# W705X.net
KiCad netlist of a schematic drawn in EAGLE
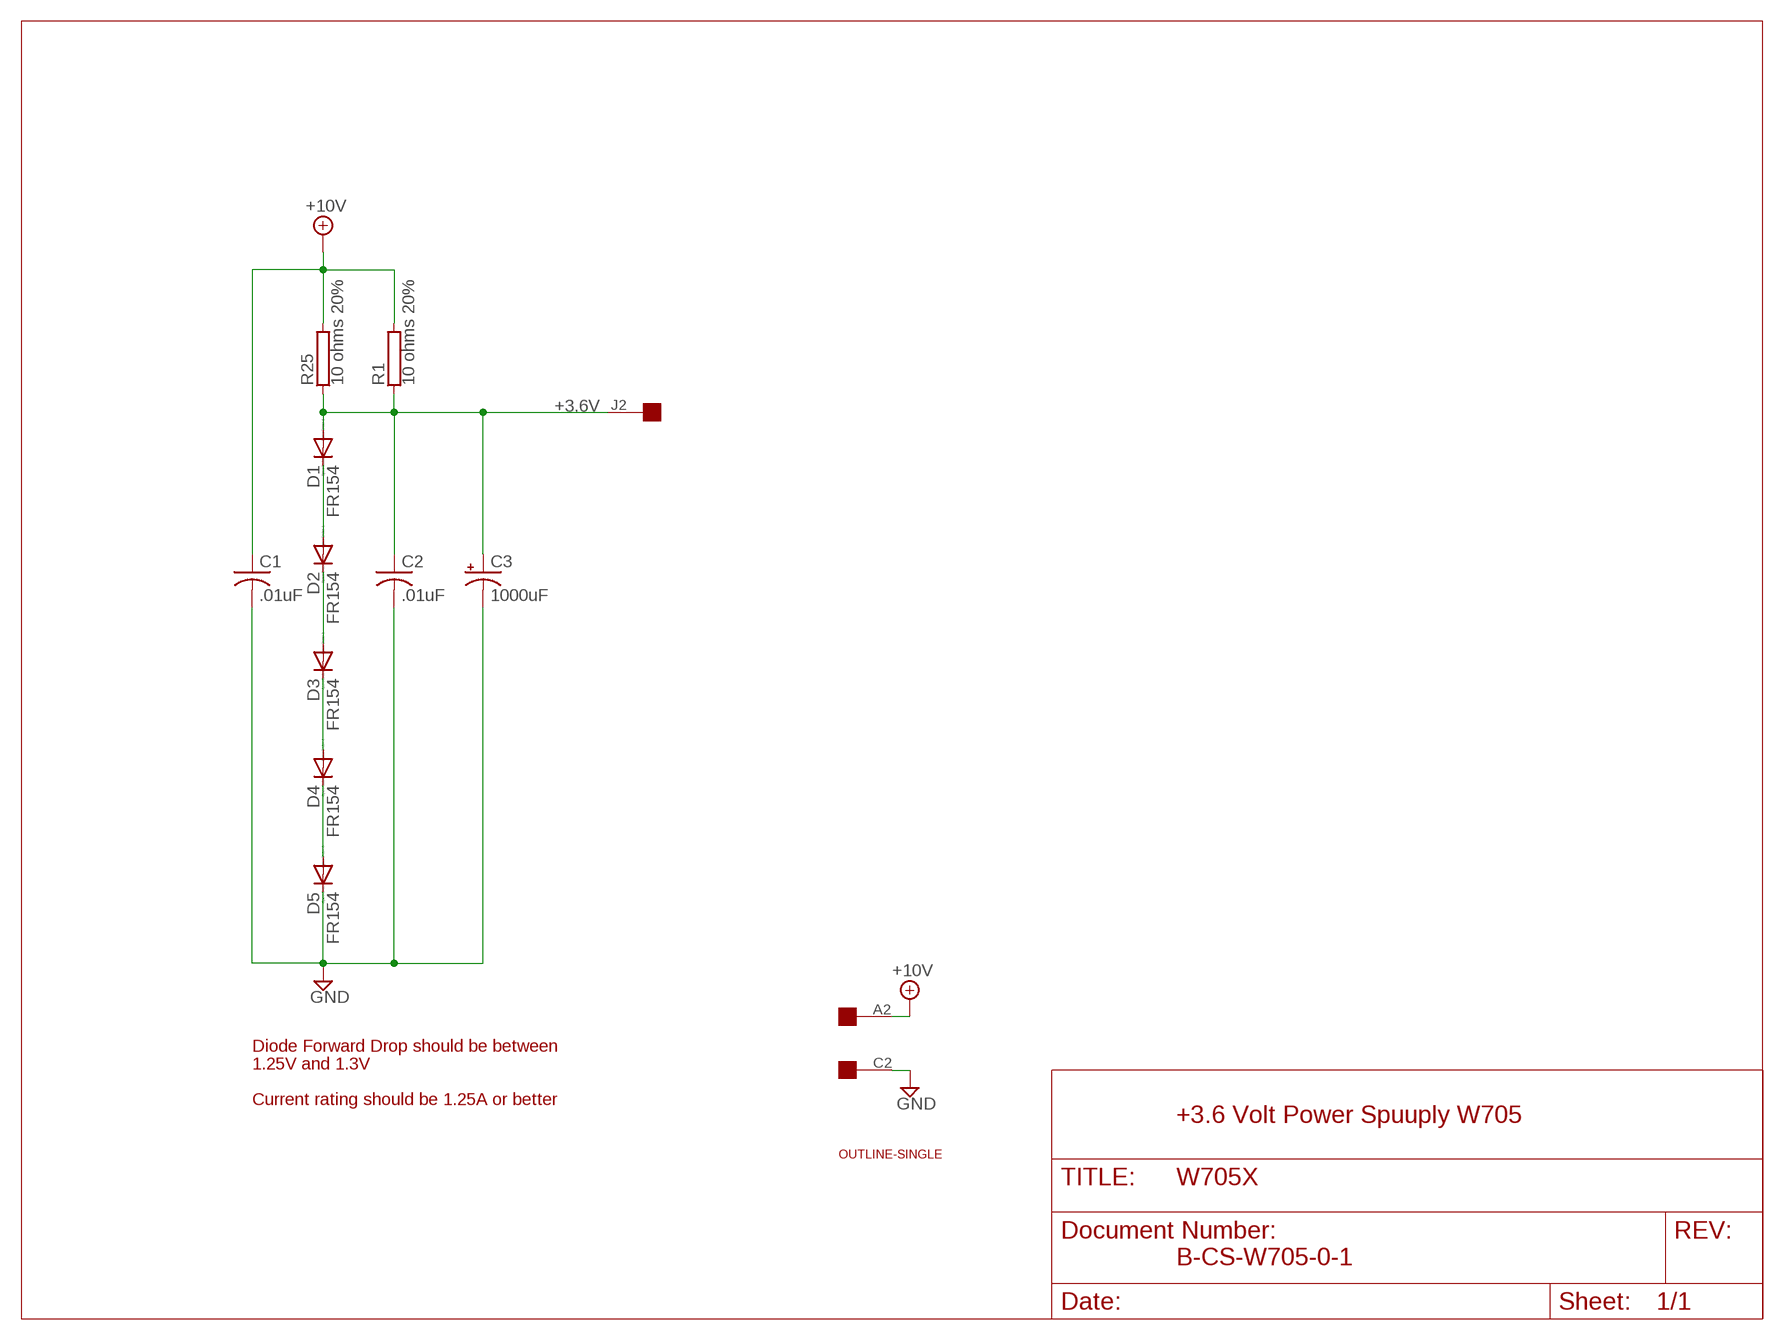
[diagram p0: schematic, sheet 1]

(export (version "E")
  (design (tool "Eeschema 10.0.6"))
  (components
    (comp (ref "C1")
      (value ".01uF")
      (footprint "eagle-import:C050-025X075")
      (libsource (lib "eagle-import") (part "C-US050-025X075"))
    )
    (comp (ref "C2")
      (value ".01uF")
      (footprint "eagle-import:C050-025X075")
      (libsource (lib "eagle-import") (part "C-US050-025X075"))
    )
    (comp (ref "C3")
      (value "1000uF")
      (footprint "eagle-import:E55-25")
      (libsource (lib "eagle-import") (part "CPOL-USE55-25AXIAL"))
    )
    (comp (ref "D1")
      (value "FR154")
      (footprint "eagle-import:DO41-10")
      (libsource (lib "eagle-import") (part "1N4004"))
    )
    (comp (ref "D2")
      (value "FR154")
      (footprint "eagle-import:DO41-10")
      (libsource (lib "eagle-import") (part "1N4004"))
    )
    (comp (ref "D3")
      (value "FR154")
      (footprint "eagle-import:DO41-10")
      (libsource (lib "eagle-import") (part "1N4004"))
    )
    (comp (ref "D4")
      (value "FR154")
      (footprint "eagle-import:DO41-10")
      (libsource (lib "eagle-import") (part "1N4004"))
    )
    (comp (ref "D5")
      (value "FR154")
      (footprint "eagle-import:DO41-10")
      (libsource (lib "eagle-import") (part "1N4004"))
    )
    (comp (ref "R1")
      (value "10 ohms 20%")
      (footprint "eagle-import:KH216-8")
      (libsource (lib "eagle-import") (part "RKH216-8"))
    )
    (comp (ref "R25")
      (value "10 ohms 20%")
      (footprint "eagle-import:KH216-8")
      (libsource (lib "eagle-import") (part "RKH216-8"))
    )
    (comp (ref "U$1")
      (value "OUTLINE-SINGLE")
      (footprint "eagle-import:SINGLE")
      (libsource (lib "eagle-import") (part "OUTLINE-SINGLE"))
    )
    (comp (ref "U$2")
      (value "EDGE-1")
      (footprint "eagle-import:EDGE-CON1")
      (libsource (lib "eagle-import") (part "EDGE-1"))
    )
  )
  (nets
    (net (code "1") (name "+10V") (class "Default")
      (node (ref "C1") (pin "1") (pinfunction "1_1") (pintype "passive"))
      (node (ref "R1") (pin "2") (pinfunction "2_2") (pintype "passive"))
      (node (ref "R25") (pin "2") (pinfunction "2_2") (pintype "passive"))
      (node (ref "U$2") (pin "A2") (pinfunction "1_A2") (pintype "bidirectional"))
    )
    (net (code "2") (name "/+3.6V") (class "Default")
      (node (ref "C2") (pin "1") (pinfunction "1_1") (pintype "passive"))
      (node (ref "C3") (pin "+") (pinfunction "+_+") (pintype "passive"))
      (node (ref "D1") (pin "A") (pinfunction "A_A") (pintype "passive"))
      (node (ref "R1") (pin "1") (pinfunction "1_1") (pintype "passive"))
      (node (ref "R25") (pin "1") (pinfunction "1_1") (pintype "passive"))
      (node (ref "U$2") (pin "J2") (pinfunction "1_J2") (pintype "bidirectional"))
    )
    (net (code "3") (name "GND") (class "Default")
      (node (ref "C1") (pin "2") (pinfunction "2_2") (pintype "passive"))
      (node (ref "C2") (pin "2") (pinfunction "2_2") (pintype "passive"))
      (node (ref "C3") (pin "-") (pinfunction "-_-") (pintype "passive"))
      (node (ref "D5") (pin "C") (pinfunction "C_C") (pintype "passive"))
      (node (ref "U$2") (pin "C2") (pinfunction "1_C2") (pintype "bidirectional"))
    )
    (net (code "4") (name "Net-(D1-PadC)") (class "Default")
      (node (ref "D1") (pin "C") (pinfunction "C_C") (pintype "passive"))
      (node (ref "D2") (pin "A") (pinfunction "A_A") (pintype "passive"))
    )
    (net (code "5") (name "Net-(D2-PadC)") (class "Default")
      (node (ref "D2") (pin "C") (pinfunction "C_C") (pintype "passive"))
      (node (ref "D3") (pin "A") (pinfunction "A_A") (pintype "passive"))
    )
    (net (code "6") (name "Net-(D3-PadC)") (class "Default")
      (node (ref "D3") (pin "C") (pinfunction "C_C") (pintype "passive"))
      (node (ref "D4") (pin "A") (pinfunction "A_A") (pintype "passive"))
    )
    (net (code "7") (name "Net-(D4-PadC)") (class "Default")
      (node (ref "D4") (pin "C") (pinfunction "C_C") (pintype "passive"))
      (node (ref "D5") (pin "A") (pinfunction "A_A") (pintype "passive"))
    )
  )
)
